# Z1.net
KiCad netlist of a schematic drawn in EAGLE
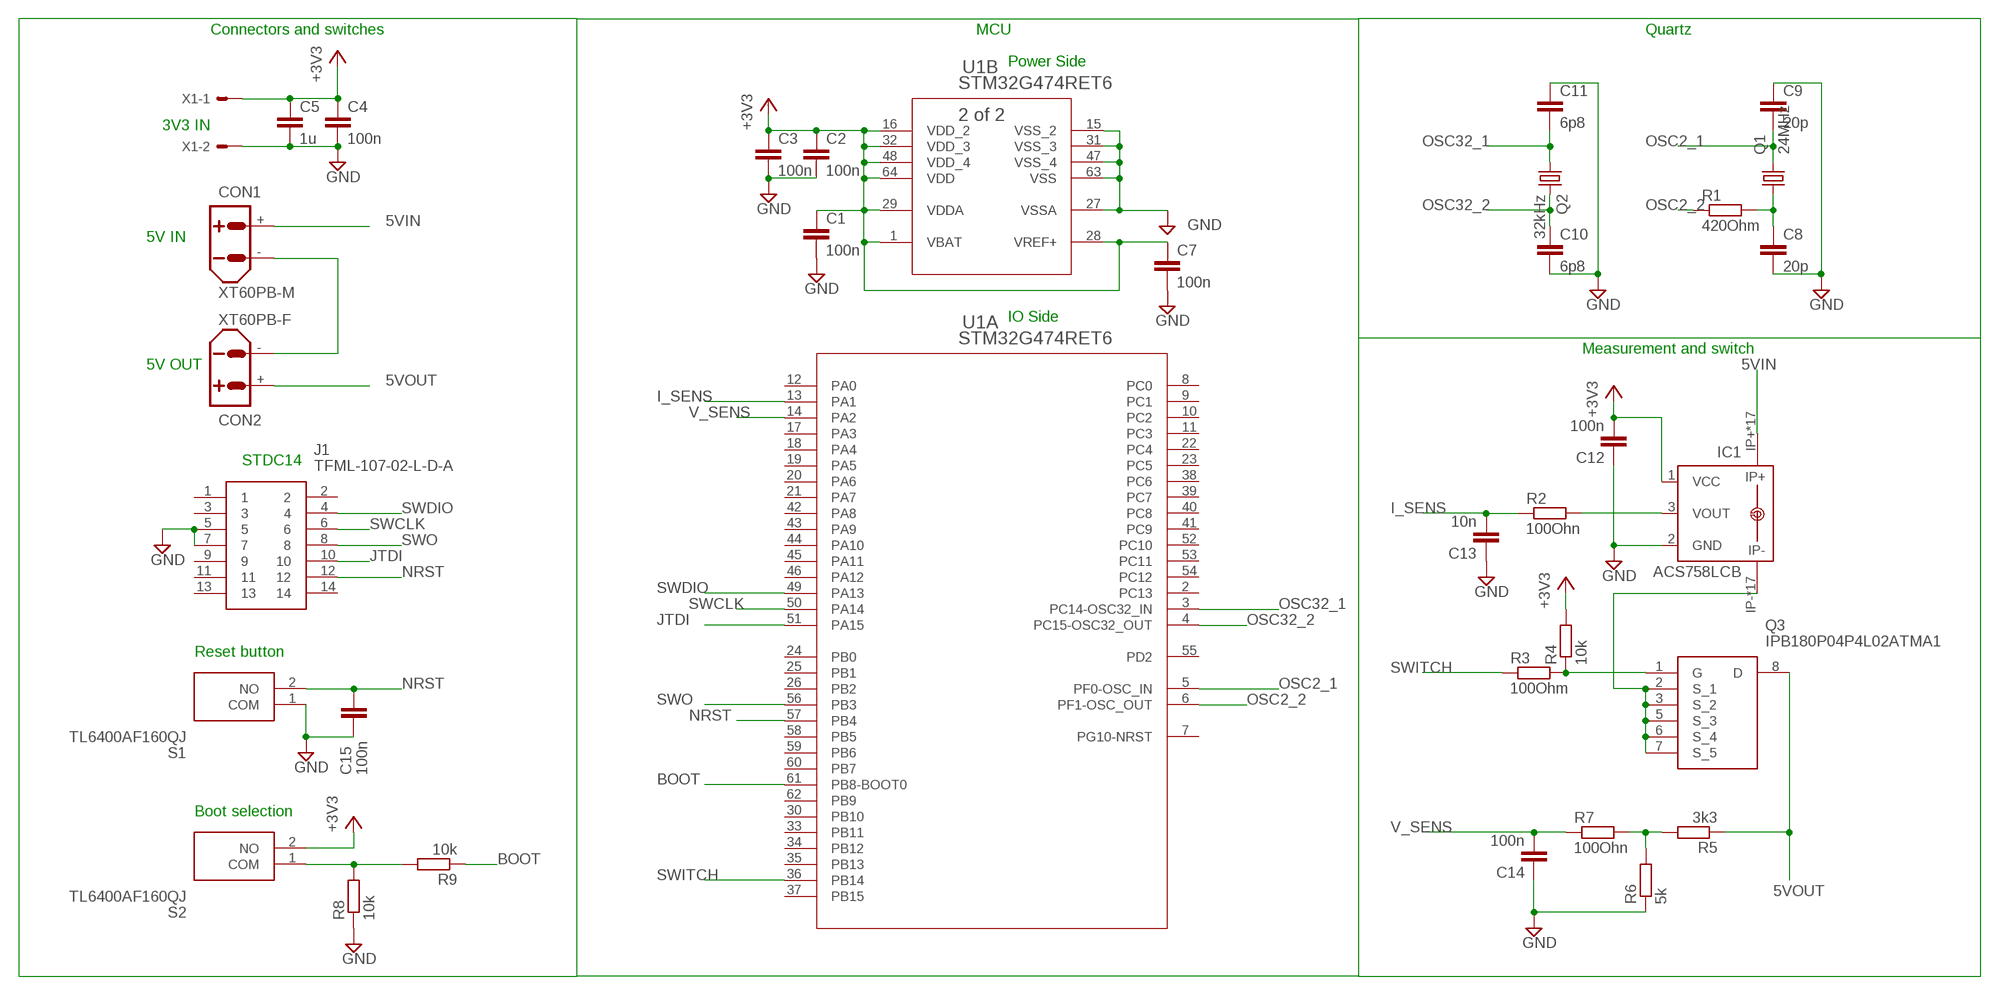
[diagram p0: schematic, sheet 1]

(export (version "E")
  (design (tool "Eeschema 10.0.6"))
  (components
    (comp (ref "C1")
      (value "100n")
      (footprint "eagle-import:C0402")
      (libsource (lib "eagle-import") (part "C-EUC0402"))
    )
    (comp (ref "C2")
      (value "100n")
      (footprint "eagle-import:C0402")
      (libsource (lib "eagle-import") (part "C-EUC0402"))
    )
    (comp (ref "C3")
      (value "100n")
      (footprint "eagle-import:C0402")
      (libsource (lib "eagle-import") (part "C-EUC0402"))
    )
    (comp (ref "C4")
      (value "100n")
      (footprint "eagle-import:C0402")
      (libsource (lib "eagle-import") (part "C-EUC0402"))
    )
    (comp (ref "C5")
      (value "1u")
      (footprint "eagle-import:C1206K")
      (libsource (lib "eagle-import") (part "C-EUC1206K"))
    )
    (comp (ref "C7")
      (value "100n")
      (footprint "eagle-import:C0402")
      (libsource (lib "eagle-import") (part "C-EUC0402"))
    )
    (comp (ref "C8")
      (value "20p")
      (footprint "eagle-import:C0402")
      (libsource (lib "eagle-import") (part "C-EUC0402"))
    )
    (comp (ref "C9")
      (value "20p")
      (footprint "eagle-import:C0402")
      (libsource (lib "eagle-import") (part "C-EUC0402"))
    )
    (comp (ref "C10")
      (value "6p8")
      (footprint "eagle-import:C0402")
      (libsource (lib "eagle-import") (part "C-EUC0402"))
    )
    (comp (ref "C11")
      (value "6p8")
      (footprint "eagle-import:C0402")
      (libsource (lib "eagle-import") (part "C-EUC0402"))
    )
    (comp (ref "C12")
      (value "100n")
      (footprint "eagle-import:C0402")
      (libsource (lib "eagle-import") (part "C-EUC0402"))
    )
    (comp (ref "C13")
      (value "10n")
      (footprint "eagle-import:C0402")
      (libsource (lib "eagle-import") (part "C-EUC0402"))
    )
    (comp (ref "C14")
      (value "100n")
      (footprint "eagle-import:C0402")
      (libsource (lib "eagle-import") (part "C-EUC0402"))
    )
    (comp (ref "C15")
      (value "100n")
      (footprint "eagle-import:C0402")
      (libsource (lib "eagle-import") (part "C-EUC0402"))
    )
    (comp (ref "CON1")
      (value "XT60PB-M")
      (footprint "eagle-import:XT60PB-M")
      (libsource (lib "eagle-import") (part "XT60PB-M"))
    )
    (comp (ref "CON2")
      (value "XT60PB-F")
      (footprint "eagle-import:XT60PB-F")
      (libsource (lib "eagle-import") (part "XT60PB-F"))
    )
    (comp (ref "IC1")
      (value "ACS758LCB")
      (footprint "eagle-import:CB-PFF")
      (fields (field (name "MPN") "ACS758LCB-050B-PFF-T"))
      (libsource (lib "eagle-import") (part "ACS758LCB-050B-PFF-T"))
    )
    (comp (ref "J1")
      (value "TFML-107-02-L-D-A")
      (footprint "eagle-import:TFML-107-02-XXX-D-A")
      (fields (field (name "MOUSER_PART_NUMBER") "200-TFML10702LDA"))
      (libsource (lib "eagle-import") (part "TFML-107-02-L-D-A"))
    )
    (comp (ref "Q1")
      (value "24MHz")
      (footprint "eagle-import:11.4X4.5")
      (libsource (lib "eagle-import") (part "KX-K"))
    )
    (comp (ref "Q2")
      (value "32kHz")
      (footprint "eagle-import:FC-12M")
      (libsource (lib "eagle-import") (part "FC-12M"))
    )
    (comp (ref "Q3")
      (value "IPB180P04P4L02ATMA1")
      (footprint "eagle-import:IPB180P04P4L02ATMA1")
      (fields (field (name "MOUSER_PART_NUMBER") "726-IPB180P04P4L02AT"))
      (libsource (lib "eagle-import") (part "IPB180P04P4L02ATMA1"))
    )
    (comp (ref "R1")
      (value "420Ohm")
      (footprint "eagle-import:R0603")
      (libsource (lib "eagle-import") (part "R-EU_R0603"))
    )
    (comp (ref "R2")
      (value "100Ohn")
      (footprint "eagle-import:R0603")
      (libsource (lib "eagle-import") (part "R-EU_R0603"))
    )
    (comp (ref "R3")
      (value "100Ohm")
      (footprint "eagle-import:R0603")
      (libsource (lib "eagle-import") (part "R-EU_R0603"))
    )
    (comp (ref "R4")
      (value "10k")
      (footprint "eagle-import:R0603")
      (libsource (lib "eagle-import") (part "R-EU_R0603"))
    )
    (comp (ref "R5")
      (value "3k3")
      (footprint "eagle-import:R0603")
      (libsource (lib "eagle-import") (part "R-EU_R0603"))
    )
    (comp (ref "R6")
      (value "5k")
      (footprint "eagle-import:R0603")
      (libsource (lib "eagle-import") (part "R-EU_R0603"))
    )
    (comp (ref "R7")
      (value "100Ohn")
      (footprint "eagle-import:R0603")
      (libsource (lib "eagle-import") (part "R-EU_R0603"))
    )
    (comp (ref "R8")
      (value "10k")
      (footprint "eagle-import:R0603")
      (libsource (lib "eagle-import") (part "R-EU_R0603"))
    )
    (comp (ref "R9")
      (value "10k")
      (footprint "eagle-import:R0603")
      (libsource (lib "eagle-import") (part "R-EU_R0603"))
    )
    (comp (ref "S1")
      (value "TL6400AF160QJ")
      (footprint "eagle-import:TL6400AF160QJ")
      (fields (field (name "MOUSER_PART_NUMBER") "612-TL6400AF160QJ"))
      (libsource (lib "eagle-import") (part "TL6400AF160QJ"))
    )
    (comp (ref "S2")
      (value "TL6400AF160QJ")
      (footprint "eagle-import:TL6400AF160QJ")
      (fields (field (name "MOUSER_PART_NUMBER") "612-TL6400AF160QJ"))
      (libsource (lib "eagle-import") (part "TL6400AF160QJ"))
    )
    (comp (ref "U1")
      (value "STM32G474RET6")
      (footprint "eagle-import:LQFP64-10X10MM")
      (fields (field (name "COPYRIGHT") "Copyright (C) 2022 Ultra Librarian. All rights reserved."))
      (libsource (lib "eagle-import") (part "STM32G474RET6"))
    )
    (comp (ref "X1")
      (value "KK-156-2")
      (footprint "eagle-import:KK-156-2")
      (fields (field (name "MF") "MOLEX"))
      (libsource (lib "eagle-import") (part "KK-156-2"))
    )
  )
  (nets
    (net (code "1") (name "+3V3") (class "Default")
      (node (ref "C1") (pin "1") (pinfunction "1_1") (pintype "passive"))
      (node (ref "C12") (pin "2") (pinfunction "2_2") (pintype "passive"))
      (node (ref "C2") (pin "1") (pinfunction "1_1") (pintype "passive"))
      (node (ref "C3") (pin "1") (pinfunction "1_1") (pintype "passive"))
      (node (ref "C4") (pin "1") (pinfunction "1_1") (pintype "passive"))
      (node (ref "C5") (pin "1") (pinfunction "1_1") (pintype "passive"))
      (node (ref "C7") (pin "1") (pinfunction "1_1") (pintype "passive"))
      (node (ref "IC1") (pin "1") (pinfunction "VCC_1") (pintype "power_in"))
      (node (ref "R4") (pin "2") (pinfunction "2_2") (pintype "passive"))
      (node (ref "S2") (pin "2") (pinfunction "NO_2") (pintype "bidirectional"))
      (node (ref "U1") (pin "1") (pinfunction "VBAT_1") (pintype "power_in"))
      (node (ref "U1") (pin "16") (pinfunction "VDD_2_16") (pintype "power_in"))
      (node (ref "U1") (pin "28") (pinfunction "VREF+_28") (pintype "power_in"))
      (node (ref "U1") (pin "29") (pinfunction "VDDA_29") (pintype "power_in"))
      (node (ref "U1") (pin "32") (pinfunction "VDD_3_32") (pintype "power_in"))
      (node (ref "U1") (pin "48") (pinfunction "VDD_4_48") (pintype "power_in"))
      (node (ref "U1") (pin "64") (pinfunction "VDD_64") (pintype "power_in"))
      (node (ref "X1") (pin "1") (pinfunction "S_1") (pintype "passive"))
    )
    (net (code "2") (name "/5VIN") (class "Default")
      (node (ref "CON1") (pin "+") (pinfunction "+_+") (pintype "power_in"))
      (node (ref "IC1") (pin "IP+") (pinfunction "IP+_IP+") (pintype "passive"))
      (node (ref "IC1") (pin "IP+@10") (pinfunction "IP+_IP+@10") (pintype "passive"))
      (node (ref "IC1") (pin "IP+@11") (pinfunction "IP+_IP+@11") (pintype "passive"))
      (node (ref "IC1") (pin "IP+@12") (pinfunction "IP+_IP+@12") (pintype "passive"))
      (node (ref "IC1") (pin "IP+@13") (pinfunction "IP+_IP+@13") (pintype "passive"))
      (node (ref "IC1") (pin "IP+@14") (pinfunction "IP+_IP+@14") (pintype "passive"))
      (node (ref "IC1") (pin "IP+@15") (pinfunction "IP+_IP+@15") (pintype "passive"))
      (node (ref "IC1") (pin "IP+@16") (pinfunction "IP+_IP+@16") (pintype "passive"))
      (node (ref "IC1") (pin "IP+@17") (pinfunction "IP+_IP+@17") (pintype "passive"))
      (node (ref "IC1") (pin "IP+@2") (pinfunction "IP+_IP+@2") (pintype "passive"))
      (node (ref "IC1") (pin "IP+@3") (pinfunction "IP+_IP+@3") (pintype "passive"))
      (node (ref "IC1") (pin "IP+@4") (pinfunction "IP+_IP+@4") (pintype "passive"))
      (node (ref "IC1") (pin "IP+@5") (pinfunction "IP+_IP+@5") (pintype "passive"))
      (node (ref "IC1") (pin "IP+@6") (pinfunction "IP+_IP+@6") (pintype "passive"))
      (node (ref "IC1") (pin "IP+@7") (pinfunction "IP+_IP+@7") (pintype "passive"))
      (node (ref "IC1") (pin "IP+@8") (pinfunction "IP+_IP+@8") (pintype "passive"))
      (node (ref "IC1") (pin "IP+@9") (pinfunction "IP+_IP+@9") (pintype "passive"))
    )
    (net (code "3") (name "/5VOUT") (class "Default")
      (node (ref "CON2") (pin "+") (pinfunction "+_+") (pintype "power_in"))
      (node (ref "Q3") (pin "8") (pinfunction "D_8") (pintype "bidirectional"))
      (node (ref "R5") (pin "1") (pinfunction "1_1") (pintype "passive"))
    )
    (net (code "4") (name "/BOOT") (class "Default")
      (node (ref "R9") (pin "1") (pinfunction "1_1") (pintype "passive"))
      (node (ref "U1") (pin "61") (pinfunction "PB8-BOOT0_61") (pintype "bidirectional"))
    )
    (net (code "5") (name "/I_SENS") (class "Default")
      (node (ref "C13") (pin "2") (pinfunction "2_2") (pintype "passive"))
      (node (ref "R2") (pin "1") (pinfunction "1_1") (pintype "passive"))
      (node (ref "U1") (pin "13") (pinfunction "PA1_13") (pintype "bidirectional"))
    )
    (net (code "6") (name "/JTDI") (class "Default")
      (node (ref "J1") (pin "10") (pinfunction "10_10") (pintype "bidirectional"))
      (node (ref "U1") (pin "51") (pinfunction "PA15_51") (pintype "bidirectional"))
    )
    (net (code "7") (name "/NRST") (class "Default")
      (node (ref "C15") (pin "1") (pinfunction "1_1") (pintype "passive"))
      (node (ref "J1") (pin "12") (pinfunction "12_12") (pintype "bidirectional"))
      (node (ref "S1") (pin "2") (pinfunction "NO_2") (pintype "bidirectional"))
      (node (ref "U1") (pin "57") (pinfunction "PB4_57") (pintype "bidirectional"))
    )
    (net (code "8") (name "/OSC2_1") (class "Default")
      (node (ref "C9") (pin "2") (pinfunction "2_2") (pintype "passive"))
      (node (ref "Q1") (pin "2") (pinfunction "2_2") (pintype "passive"))
      (node (ref "U1") (pin "5") (pinfunction "PF0-OSC_IN_5") (pintype "bidirectional"))
    )
    (net (code "9") (name "/OSC2_2") (class "Default")
      (node (ref "R1") (pin "1") (pinfunction "1_1") (pintype "passive"))
      (node (ref "U1") (pin "6") (pinfunction "PF1-OSC_OUT_6") (pintype "bidirectional"))
    )
    (net (code "10") (name "/OSC32_1") (class "Default")
      (node (ref "C11") (pin "2") (pinfunction "2_2") (pintype "passive"))
      (node (ref "Q2") (pin "1") (pinfunction "1_1") (pintype "passive"))
      (node (ref "U1") (pin "3") (pinfunction "PC14-OSC32_IN_3") (pintype "bidirectional"))
    )
    (net (code "11") (name "/OSC32_2") (class "Default")
      (node (ref "C10") (pin "1") (pinfunction "1_1") (pintype "passive"))
      (node (ref "Q2") (pin "2") (pinfunction "2_2") (pintype "passive"))
      (node (ref "U1") (pin "4") (pinfunction "PC15-OSC32_OUT_4") (pintype "bidirectional"))
    )
    (net (code "12") (name "/SWCLK") (class "Default")
      (node (ref "J1") (pin "6") (pinfunction "6_6") (pintype "bidirectional"))
      (node (ref "U1") (pin "50") (pinfunction "PA14_50") (pintype "bidirectional"))
    )
    (net (code "13") (name "/SWDIO") (class "Default")
      (node (ref "J1") (pin "4") (pinfunction "4_4") (pintype "bidirectional"))
      (node (ref "U1") (pin "49") (pinfunction "PA13_49") (pintype "bidirectional"))
    )
    (net (code "14") (name "/SWITCH") (class "Default")
      (node (ref "R3") (pin "1") (pinfunction "1_1") (pintype "passive"))
      (node (ref "U1") (pin "36") (pinfunction "PB14_36") (pintype "bidirectional"))
    )
    (net (code "15") (name "/SWO") (class "Default")
      (node (ref "J1") (pin "8") (pinfunction "8_8") (pintype "bidirectional"))
      (node (ref "U1") (pin "56") (pinfunction "PB3_56") (pintype "bidirectional"))
    )
    (net (code "16") (name "/V_SENS") (class "Default")
      (node (ref "C14") (pin "2") (pinfunction "2_2") (pintype "passive"))
      (node (ref "R7") (pin "1") (pinfunction "1_1") (pintype "passive"))
      (node (ref "U1") (pin "14") (pinfunction "PA2_14") (pintype "bidirectional"))
    )
    (net (code "17") (name "GND") (class "Default")
      (node (ref "C1") (pin "2") (pinfunction "2_2") (pintype "passive"))
      (node (ref "C10") (pin "2") (pinfunction "2_2") (pintype "passive"))
      (node (ref "C11") (pin "1") (pinfunction "1_1") (pintype "passive"))
      (node (ref "C12") (pin "1") (pinfunction "1_1") (pintype "passive"))
      (node (ref "C13") (pin "1") (pinfunction "1_1") (pintype "passive"))
      (node (ref "C14") (pin "1") (pinfunction "1_1") (pintype "passive"))
      (node (ref "C15") (pin "2") (pinfunction "2_2") (pintype "passive"))
      (node (ref "C2") (pin "2") (pinfunction "2_2") (pintype "passive"))
      (node (ref "C3") (pin "2") (pinfunction "2_2") (pintype "passive"))
      (node (ref "C4") (pin "2") (pinfunction "2_2") (pintype "passive"))
      (node (ref "C5") (pin "2") (pinfunction "2_2") (pintype "passive"))
      (node (ref "C7") (pin "2") (pinfunction "2_2") (pintype "passive"))
      (node (ref "C8") (pin "2") (pinfunction "2_2") (pintype "passive"))
      (node (ref "C9") (pin "1") (pinfunction "1_1") (pintype "passive"))
      (node (ref "IC1") (pin "2") (pinfunction "GND_2") (pintype "power_in"))
      (node (ref "J1") (pin "5") (pinfunction "5_5") (pintype "bidirectional"))
      (node (ref "J1") (pin "7") (pinfunction "7_7") (pintype "bidirectional"))
      (node (ref "R6") (pin "1") (pinfunction "1_1") (pintype "passive"))
      (node (ref "R8") (pin "1") (pinfunction "1_1") (pintype "passive"))
      (node (ref "S1") (pin "1") (pinfunction "COM_1") (pintype "bidirectional"))
      (node (ref "U1") (pin "15") (pinfunction "VSS_2_15") (pintype "power_in"))
      (node (ref "U1") (pin "27") (pinfunction "VSSA_27") (pintype "power_in"))
      (node (ref "U1") (pin "31") (pinfunction "VSS_3_31") (pintype "power_in"))
      (node (ref "U1") (pin "47") (pinfunction "VSS_4_47") (pintype "power_in"))
      (node (ref "U1") (pin "63") (pinfunction "VSS_63") (pintype "power_in"))
      (node (ref "X1") (pin "2") (pinfunction "S_2") (pintype "passive"))
    )
    (net (code "18") (name "Net-(C8-Pad1)") (class "Default")
      (node (ref "C8") (pin "1") (pinfunction "1_1") (pintype "passive"))
      (node (ref "Q1") (pin "1") (pinfunction "1_1") (pintype "passive"))
      (node (ref "R1") (pin "2") (pinfunction "2_2") (pintype "passive"))
    )
    (net (code "19") (name "Net-(CON1-Pad-)") (class "Default")
      (node (ref "CON1") (pin "-") (pinfunction "-_-") (pintype "power_in"))
      (node (ref "CON2") (pin "-") (pinfunction "-_-") (pintype "power_in"))
    )
    (net (code "20") (name "Net-(IC1-VOUT)") (class "Default")
      (node (ref "IC1") (pin "3") (pinfunction "VOUT_3") (pintype "output"))
      (node (ref "R2") (pin "2") (pinfunction "2_2") (pintype "passive"))
    )
    (net (code "21") (name "Net-(Q3-G)") (class "Default")
      (node (ref "Q3") (pin "1") (pinfunction "G_1") (pintype "bidirectional"))
      (node (ref "R3") (pin "2") (pinfunction "2_2") (pintype "passive"))
      (node (ref "R4") (pin "1") (pinfunction "1_1") (pintype "passive"))
    )
    (net (code "22") (name "Net-(Q3-S_1)") (class "Default")
      (node (ref "IC1") (pin "IP-") (pinfunction "IP-_IP-") (pintype "passive"))
      (node (ref "IC1") (pin "IP-@10") (pinfunction "IP-_IP-@10") (pintype "passive"))
      (node (ref "IC1") (pin "IP-@11") (pinfunction "IP-_IP-@11") (pintype "passive"))
      (node (ref "IC1") (pin "IP-@12") (pinfunction "IP-_IP-@12") (pintype "passive"))
      (node (ref "IC1") (pin "IP-@13") (pinfunction "IP-_IP-@13") (pintype "passive"))
      (node (ref "IC1") (pin "IP-@14") (pinfunction "IP-_IP-@14") (pintype "passive"))
      (node (ref "IC1") (pin "IP-@15") (pinfunction "IP-_IP-@15") (pintype "passive"))
      (node (ref "IC1") (pin "IP-@16") (pinfunction "IP-_IP-@16") (pintype "passive"))
      (node (ref "IC1") (pin "IP-@17") (pinfunction "IP-_IP-@17") (pintype "passive"))
      (node (ref "IC1") (pin "IP-@2") (pinfunction "IP-_IP-@2") (pintype "passive"))
      (node (ref "IC1") (pin "IP-@3") (pinfunction "IP-_IP-@3") (pintype "passive"))
      (node (ref "IC1") (pin "IP-@4") (pinfunction "IP-_IP-@4") (pintype "passive"))
      (node (ref "IC1") (pin "IP-@5") (pinfunction "IP-_IP-@5") (pintype "passive"))
      (node (ref "IC1") (pin "IP-@6") (pinfunction "IP-_IP-@6") (pintype "passive"))
      (node (ref "IC1") (pin "IP-@7") (pinfunction "IP-_IP-@7") (pintype "passive"))
      (node (ref "IC1") (pin "IP-@8") (pinfunction "IP-_IP-@8") (pintype "passive"))
      (node (ref "IC1") (pin "IP-@9") (pinfunction "IP-_IP-@9") (pintype "passive"))
      (node (ref "Q3") (pin "2") (pinfunction "S_1_2") (pintype "bidirectional"))
      (node (ref "Q3") (pin "3") (pinfunction "S_2_3") (pintype "bidirectional"))
      (node (ref "Q3") (pin "5") (pinfunction "S_3_5") (pintype "bidirectional"))
      (node (ref "Q3") (pin "6") (pinfunction "S_4_6") (pintype "bidirectional"))
      (node (ref "Q3") (pin "7") (pinfunction "S_5_7") (pintype "bidirectional"))
    )
    (net (code "23") (name "Net-(R5-Pad2)") (class "Default")
      (node (ref "R5") (pin "2") (pinfunction "2_2") (pintype "passive"))
      (node (ref "R6") (pin "2") (pinfunction "2_2") (pintype "passive"))
      (node (ref "R7") (pin "2") (pinfunction "2_2") (pintype "passive"))
    )
    (net (code "24") (name "Net-(S2-COM)") (class "Default")
      (node (ref "R8") (pin "2") (pinfunction "2_2") (pintype "passive"))
      (node (ref "R9") (pin "2") (pinfunction "2_2") (pintype "passive"))
      (node (ref "S2") (pin "1") (pinfunction "COM_1") (pintype "bidirectional"))
    )
    (net (code "25") (name "unconnected-(J1-Pad1)") (class "Default")
      (node (ref "J1") (pin "1") (pinfunction "1_1") (pintype "bidirectional"))
    )
    (net (code "26") (name "unconnected-(J1-Pad2)") (class "Default")
      (node (ref "J1") (pin "2") (pinfunction "2_2") (pintype "bidirectional"))
    )
    (net (code "27") (name "unconnected-(J1-Pad3)") (class "Default")
      (node (ref "J1") (pin "3") (pinfunction "3_3") (pintype "bidirectional"))
    )
    (net (code "28") (name "unconnected-(J1-Pad9)") (class "Default")
      (node (ref "J1") (pin "9") (pinfunction "9_9") (pintype "bidirectional"))
    )
    (net (code "29") (name "unconnected-(J1-Pad11)") (class "Default")
      (node (ref "J1") (pin "11") (pinfunction "11_11") (pintype "bidirectional"))
    )
    (net (code "30") (name "unconnected-(J1-Pad13)") (class "Default")
      (node (ref "J1") (pin "13") (pinfunction "13_13") (pintype "bidirectional"))
    )
    (net (code "31") (name "unconnected-(J1-Pad14)") (class "Default")
      (node (ref "J1") (pin "14") (pinfunction "14_14") (pintype "bidirectional"))
    )
    (net (code "32") (name "unconnected-(U1A-PA0-Pad12)") (class "Default")
      (node (ref "U1") (pin "12") (pinfunction "PA0_12") (pintype "bidirectional"))
    )
    (net (code "33") (name "unconnected-(U1A-PA3-Pad17)") (class "Default")
      (node (ref "U1") (pin "17") (pinfunction "PA3_17") (pintype "bidirectional"))
    )
    (net (code "34") (name "unconnected-(U1A-PA4-Pad18)") (class "Default")
      (node (ref "U1") (pin "18") (pinfunction "PA4_18") (pintype "bidirectional"))
    )
    (net (code "35") (name "unconnected-(U1A-PA5-Pad19)") (class "Default")
      (node (ref "U1") (pin "19") (pinfunction "PA5_19") (pintype "bidirectional"))
    )
    (net (code "36") (name "unconnected-(U1A-PA6-Pad20)") (class "Default")
      (node (ref "U1") (pin "20") (pinfunction "PA6_20") (pintype "bidirectional"))
    )
    (net (code "37") (name "unconnected-(U1A-PA7-Pad21)") (class "Default")
      (node (ref "U1") (pin "21") (pinfunction "PA7_21") (pintype "bidirectional"))
    )
    (net (code "38") (name "unconnected-(U1A-PA8-Pad42)") (class "Default")
      (node (ref "U1") (pin "42") (pinfunction "PA8_42") (pintype "bidirectional"))
    )
    (net (code "39") (name "unconnected-(U1A-PA9-Pad43)") (class "Default")
      (node (ref "U1") (pin "43") (pinfunction "PA9_43") (pintype "bidirectional"))
    )
    (net (code "40") (name "unconnected-(U1A-PA10-Pad44)") (class "Default")
      (node (ref "U1") (pin "44") (pinfunction "PA10_44") (pintype "bidirectional"))
    )
    (net (code "41") (name "unconnected-(U1A-PA11-Pad45)") (class "Default")
      (node (ref "U1") (pin "45") (pinfunction "PA11_45") (pintype "bidirectional"))
    )
    (net (code "42") (name "unconnected-(U1A-PA12-Pad46)") (class "Default")
      (node (ref "U1") (pin "46") (pinfunction "PA12_46") (pintype "bidirectional"))
    )
    (net (code "43") (name "unconnected-(U1A-PB0-Pad24)") (class "Default")
      (node (ref "U1") (pin "24") (pinfunction "PB0_24") (pintype "bidirectional"))
    )
    (net (code "44") (name "unconnected-(U1A-PB1-Pad25)") (class "Default")
      (node (ref "U1") (pin "25") (pinfunction "PB1_25") (pintype "bidirectional"))
    )
    (net (code "45") (name "unconnected-(U1A-PB2-Pad26)") (class "Default")
      (node (ref "U1") (pin "26") (pinfunction "PB2_26") (pintype "bidirectional"))
    )
    (net (code "46") (name "unconnected-(U1A-PB5-Pad58)") (class "Default")
      (node (ref "U1") (pin "58") (pinfunction "PB5_58") (pintype "bidirectional"))
    )
    (net (code "47") (name "unconnected-(U1A-PB6-Pad59)") (class "Default")
      (node (ref "U1") (pin "59") (pinfunction "PB6_59") (pintype "bidirectional"))
    )
    (net (code "48") (name "unconnected-(U1A-PB7-Pad60)") (class "Default")
      (node (ref "U1") (pin "60") (pinfunction "PB7_60") (pintype "bidirectional"))
    )
    (net (code "49") (name "unconnected-(U1A-PB9-Pad62)") (class "Default")
      (node (ref "U1") (pin "62") (pinfunction "PB9_62") (pintype "bidirectional"))
    )
    (net (code "50") (name "unconnected-(U1A-PB10-Pad30)") (class "Default")
      (node (ref "U1") (pin "30") (pinfunction "PB10_30") (pintype "bidirectional"))
    )
    (net (code "51") (name "unconnected-(U1A-PB11-Pad33)") (class "Default")
      (node (ref "U1") (pin "33") (pinfunction "PB11_33") (pintype "bidirectional"))
    )
    (net (code "52") (name "unconnected-(U1A-PB12-Pad34)") (class "Default")
      (node (ref "U1") (pin "34") (pinfunction "PB12_34") (pintype "bidirectional"))
    )
    (net (code "53") (name "unconnected-(U1A-PB13-Pad35)") (class "Default")
      (node (ref "U1") (pin "35") (pinfunction "PB13_35") (pintype "bidirectional"))
    )
    (net (code "54") (name "unconnected-(U1A-PB15-Pad37)") (class "Default")
      (node (ref "U1") (pin "37") (pinfunction "PB15_37") (pintype "bidirectional"))
    )
    (net (code "55") (name "unconnected-(U1A-PC0-Pad8)") (class "Default")
      (node (ref "U1") (pin "8") (pinfunction "PC0_8") (pintype "bidirectional"))
    )
    (net (code "56") (name "unconnected-(U1A-PC1-Pad9)") (class "Default")
      (node (ref "U1") (pin "9") (pinfunction "PC1_9") (pintype "bidirectional"))
    )
    (net (code "57") (name "unconnected-(U1A-PC2-Pad10)") (class "Default")
      (node (ref "U1") (pin "10") (pinfunction "PC2_10") (pintype "bidirectional"))
    )
    (net (code "58") (name "unconnected-(U1A-PC3-Pad11)") (class "Default")
      (node (ref "U1") (pin "11") (pinfunction "PC3_11") (pintype "bidirectional"))
    )
    (net (code "59") (name "unconnected-(U1A-PC4-Pad22)") (class "Default")
      (node (ref "U1") (pin "22") (pinfunction "PC4_22") (pintype "bidirectional"))
    )
    (net (code "60") (name "unconnected-(U1A-PC5-Pad23)") (class "Default")
      (node (ref "U1") (pin "23") (pinfunction "PC5_23") (pintype "bidirectional"))
    )
    (net (code "61") (name "unconnected-(U1A-PC6-Pad38)") (class "Default")
      (node (ref "U1") (pin "38") (pinfunction "PC6_38") (pintype "bidirectional"))
    )
    (net (code "62") (name "unconnected-(U1A-PC7-Pad39)") (class "Default")
      (node (ref "U1") (pin "39") (pinfunction "PC7_39") (pintype "bidirectional"))
    )
    (net (code "63") (name "unconnected-(U1A-PC8-Pad40)") (class "Default")
      (node (ref "U1") (pin "40") (pinfunction "PC8_40") (pintype "bidirectional"))
    )
    (net (code "64") (name "unconnected-(U1A-PC9-Pad41)") (class "Default")
      (node (ref "U1") (pin "41") (pinfunction "PC9_41") (pintype "bidirectional"))
    )
    (net (code "65") (name "unconnected-(U1A-PC10-Pad52)") (class "Default")
      (node (ref "U1") (pin "52") (pinfunction "PC10_52") (pintype "bidirectional"))
    )
    (net (code "66") (name "unconnected-(U1A-PC11-Pad53)") (class "Default")
      (node (ref "U1") (pin "53") (pinfunction "PC11_53") (pintype "bidirectional"))
    )
    (net (code "67") (name "unconnected-(U1A-PC12-Pad54)") (class "Default")
      (node (ref "U1") (pin "54") (pinfunction "PC12_54") (pintype "bidirectional"))
    )
    (net (code "68") (name "unconnected-(U1A-PC13-Pad2)") (class "Default")
      (node (ref "U1") (pin "2") (pinfunction "PC13_2") (pintype "bidirectional"))
    )
    (net (code "69") (name "unconnected-(U1A-PD2-Pad55)") (class "Default")
      (node (ref "U1") (pin "55") (pinfunction "PD2_55") (pintype "bidirectional"))
    )
    (net (code "70") (name "unconnected-(U1A-PG10-NRST-Pad7)") (class "Default")
      (node (ref "U1") (pin "7") (pinfunction "PG10-NRST_7") (pintype "bidirectional"))
    )
  )
)
